# robotShield_USB.net
KiCad netlist of a schematic drawn in Altium Designer
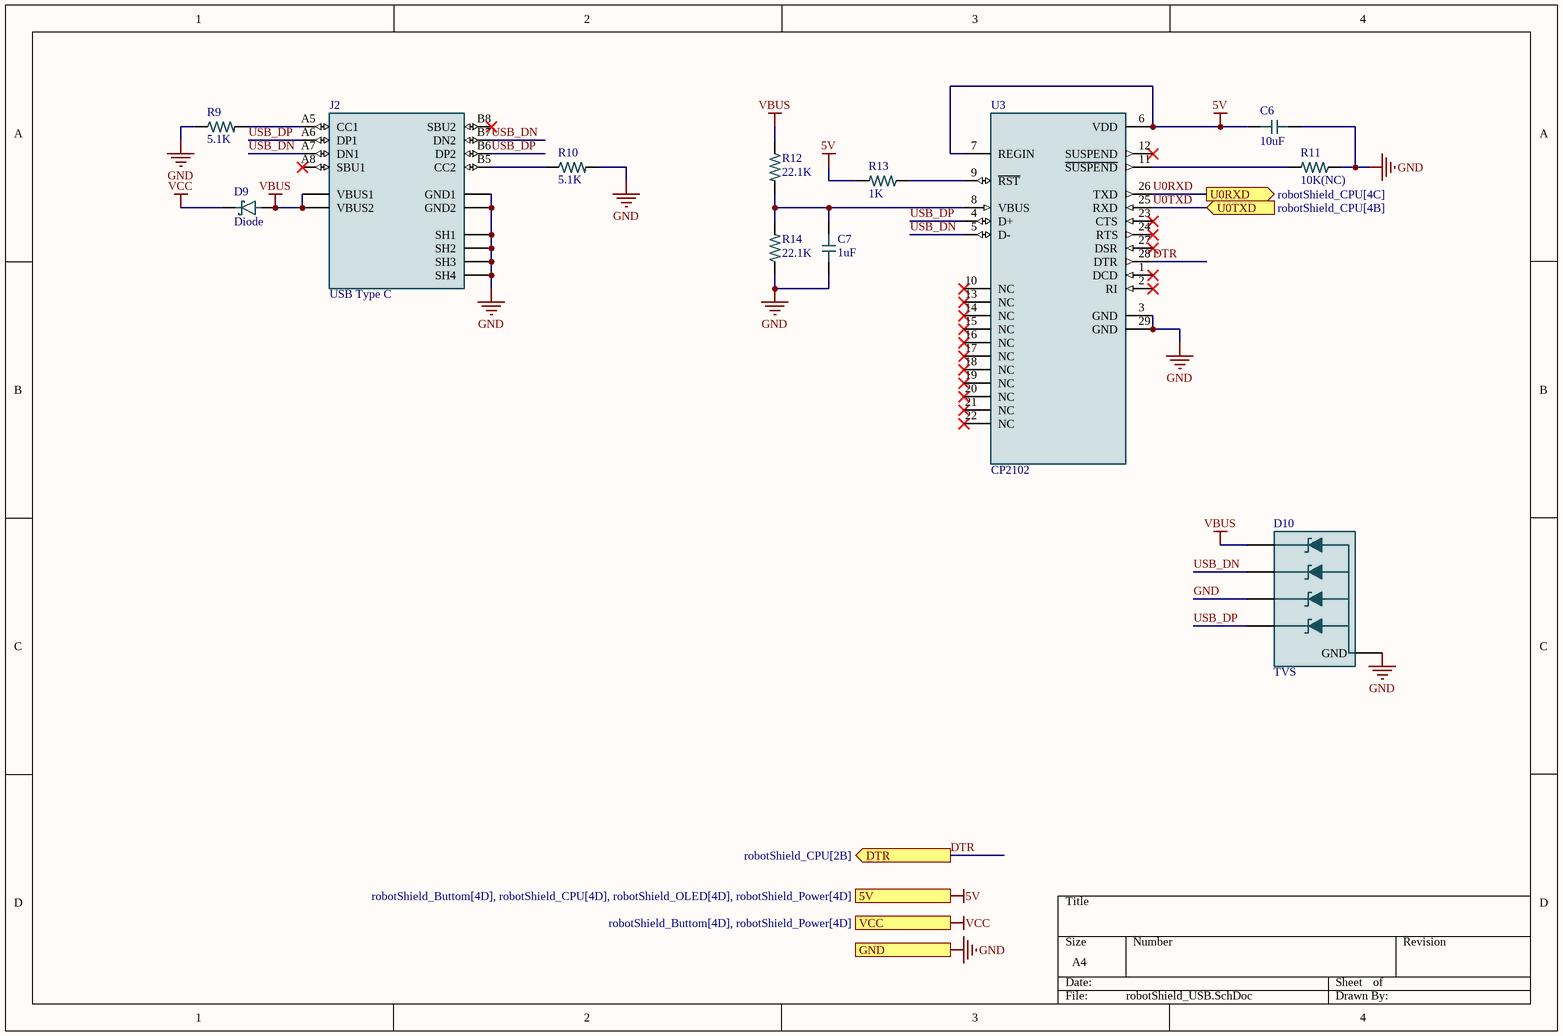
[diagram p0: robotShield_USB.SchDoc]

(export (version "E")
  (design (tool "Eeschema 10.0.6"))
  (components
    (comp (ref "C6")
      (value "10uF")
      (footprint "CAP0603")
      (description "CAP SMD")
      (fields (field (name "MF") "AVX") (field (name "MP") "LD031A101GAB2A"))
      (libsource (lib "Hossein72T") (part "Capacitor"))
    )
    (comp (ref "C7")
      (value "1uF")
      (footprint "CAP0603")
      (description "CAP SMD")
      (fields (field (name "MF") "AVX") (field (name "MP") "LD031A101GAB2A"))
      (libsource (lib "Hossein72T") (part "Capacitor"))
    )
    (comp (ref "D9")
      (value "Diode")
      (footprint "MBR0520LT3G")
      (description "Schottky Diode")
      (fields (field (name "MF") "Diotec Semiconductor") (field (name "MP") "S1M"))
      (libsource (lib "Hossein72T") (part "Schottky Diode"))
    )
    (comp (ref "D10")
      (value "TVS")
      (footprint "TVS-SE05T1D12GZ")
      (description "ESD8104MUTAG, Quad Uni-Directional ESD Protection Diode, 10-Pin UDFN")
      (fields (field (name "MP") "ESD8104MUTAG") (field (name "MF") "ON Semiconductor"))
      (libsource (lib "Hossein72T") (part "TVS_SE05NRC14GT"))
    )
    (comp (ref "J2")
      (value "USB Type C")
      (footprint "USB_Type_C_16pin")
      (description "USB Type C - Connector, Top-mount SMT, 16pos ¦ Molex Incorporated 217179-0001")
      (fields (field (name "MF") "Molex") (field (name "MP") "217179-0001"))
      (libsource (lib "Hossein72T") (part "USB_Type_C _16pin"))
    )
    (comp (ref "R9")
      (value "5.1K")
      (footprint "RES0603")
      (description "RES 0.27 OHM 1% 1/10W")
      (fields (field (name "MP") "3-1879460-5") (field (name "MF") "TE Connectivity"))
      (libsource (lib "Hossein72T") (part "Resistor"))
    )
    (comp (ref "R10")
      (value "5.1K")
      (footprint "RES0603")
      (description "RES 0.27 OHM 1% 1/10W")
      (fields (field (name "MP") "3-1879460-5") (field (name "MF") "TE Connectivity"))
      (libsource (lib "Hossein72T") (part "Resistor"))
    )
    (comp (ref "R11")
      (value "10K(NC)")
      (footprint "RES0603")
      (description "RES 0.27 OHM 1% 1/10W")
      (fields (field (name "MP") "3-1879460-5") (field (name "MF") "TE Connectivity"))
      (libsource (lib "Hossein72T") (part "Resistor"))
    )
    (comp (ref "R12")
      (value "22.1K")
      (footprint "RES0603")
      (description "RES 0.27 OHM 1% 1/10W")
      (fields (field (name "MP") "3-1879460-5") (field (name "MF") "TE Connectivity"))
      (libsource (lib "Hossein72T") (part "Resistor"))
    )
    (comp (ref "R13")
      (value "1K")
      (footprint "RES0603")
      (description "RES 0.27 OHM 1% 1/10W")
      (fields (field (name "MP") "3-1879460-5") (field (name "MF") "TE Connectivity"))
      (libsource (lib "Hossein72T") (part "Resistor"))
    )
    (comp (ref "R14")
      (value "22.1K")
      (footprint "RES0603")
      (description "RES 0.27 OHM 1% 1/10W")
      (fields (field (name "MP") "3-1879460-5") (field (name "MF") "TE Connectivity"))
      (libsource (lib "Hossein72T") (part "Resistor"))
    )
    (comp (ref "U3")
      (value "CP2102")
      (footprint "CP2102")
      (description "CP2102N USB 2.0 to UART (RS232) Bridge Interface Evaluation Board")
      (fields (field (name "MF") "Silicon Labs"))
      (libsource (lib "Hossein72T") (part "CP2102"))
    )
  )
  (nets
    (net (code "1") (name "/DTR") (class "Default")
      (node (ref "U3") (pin "28") (pinfunction "DTR_28") (pintype "output"))
    )
    (net (code "2") (name "/U0RXD") (class "Default")
      (node (ref "U3") (pin "26") (pinfunction "TXD_26") (pintype "output"))
    )
    (net (code "3") (name "/U0TXD") (class "Default")
      (node (ref "U3") (pin "25") (pinfunction "RXD_25") (pintype "input"))
    )
    (net (code "4") (name "/USB_DN") (class "Default")
      (node (ref "D10") (pin "2") (pinfunction "I/O_2_2") (pintype "passive"))
      (node (ref "J2") (pin "A7") (pinfunction "DN1_A7") (pintype "bidirectional"))
      (node (ref "J2") (pin "B7") (pinfunction "DN2_B7") (pintype "bidirectional"))
      (node (ref "U3") (pin "5") (pinfunction "D-_5") (pintype "bidirectional"))
    )
    (net (code "5") (name "/USB_DP") (class "Default")
      (node (ref "D10") (pin "5") (pinfunction "I/O_5_5") (pintype "passive"))
      (node (ref "J2") (pin "A6") (pinfunction "DP1_A6") (pintype "bidirectional"))
      (node (ref "J2") (pin "B6") (pinfunction "DP2_B6") (pintype "bidirectional"))
      (node (ref "U3") (pin "4") (pinfunction "D+_4") (pintype "bidirectional"))
    )
    (net (code "6") (name "5V") (class "Default")
      (node (ref "C6") (pin "1") (pinfunction "1_1") (pintype "passive"))
      (node (ref "R13") (pin "2") (pinfunction "2_2") (pintype "passive"))
      (node (ref "U3") (pin "6") (pinfunction "VDD_6") (pintype "power_in"))
      (node (ref "U3") (pin "7") (pinfunction "REGIN_7") (pintype "power_in"))
    )
    (net (code "7") (name "GND") (class "Default")
      (node (ref "C6") (pin "2") (pinfunction "2_2") (pintype "passive"))
      (node (ref "C7") (pin "2") (pinfunction "2_2") (pintype "passive"))
      (node (ref "D10") (pin "3") (pinfunction "GND_3") (pintype "power_in"))
      (node (ref "D10") (pin "4") (pinfunction "I/O_4_4") (pintype "passive"))
      (node (ref "J2") (pin "A1B12") (pinfunction "GND1_A1B12") (pintype "power_in"))
      (node (ref "J2") (pin "B1A12") (pinfunction "GND2_B1A12") (pintype "power_in"))
      (node (ref "J2") (pin "SH1") (pinfunction "SH1_SH1") (pintype "passive"))
      (node (ref "J2") (pin "SH2") (pinfunction "SH2_SH2") (pintype "passive"))
      (node (ref "J2") (pin "SH3") (pinfunction "SH3_SH3") (pintype "passive"))
      (node (ref "J2") (pin "SH4") (pinfunction "SH4_SH4") (pintype "passive"))
      (node (ref "R10") (pin "2") (pinfunction "2_2") (pintype "passive"))
      (node (ref "R11") (pin "1") (pinfunction "1_1") (pintype "passive"))
      (node (ref "R14") (pin "1") (pinfunction "1_1") (pintype "passive"))
      (node (ref "R9") (pin "1") (pinfunction "1_1") (pintype "passive"))
      (node (ref "U3") (pin "29") (pinfunction "GND_29") (pintype "power_in"))
      (node (ref "U3") (pin "3") (pinfunction "GND_3") (pintype "power_in"))
    )
    (net (code "8") (name "Net-(J2-CC1)") (class "Default")
      (node (ref "J2") (pin "A5") (pinfunction "CC1_A5") (pintype "bidirectional"))
      (node (ref "R9") (pin "2") (pinfunction "2_2") (pintype "passive"))
    )
    (net (code "9") (name "Net-(J2-CC2)") (class "Default")
      (node (ref "J2") (pin "B5") (pinfunction "CC2_B5") (pintype "bidirectional"))
      (node (ref "R10") (pin "1") (pinfunction "1_1") (pintype "passive"))
    )
    (net (code "10") (name "Net-(U3-VBUS)") (class "Default")
      (node (ref "C7") (pin "1") (pinfunction "1_1") (pintype "passive"))
      (node (ref "R12") (pin "2") (pinfunction "2_2") (pintype "passive"))
      (node (ref "R14") (pin "2") (pinfunction "2_2") (pintype "passive"))
      (node (ref "U3") (pin "8") (pinfunction "VBUS_8") (pintype "input"))
    )
    (net (code "11") (name "Net-(U3-~{RST})") (class "Default")
      (node (ref "R13") (pin "1") (pinfunction "1_1") (pintype "passive"))
      (node (ref "U3") (pin "9") (pinfunction "~{RST}_9") (pintype "bidirectional"))
    )
    (net (code "12") (name "Net-(U3-~{SUSPEND})") (class "Default")
      (node (ref "R11") (pin "2") (pinfunction "2_2") (pintype "passive"))
      (node (ref "U3") (pin "11") (pinfunction "~{SUSPEND}_11") (pintype "output"))
    )
    (net (code "13") (name "VBUS") (class "Default")
      (node (ref "D10") (pin "1") (pinfunction "I/O_1_1") (pintype "passive"))
      (node (ref "D9") (pin "A") (pinfunction "A_A") (pintype "passive"))
      (node (ref "J2") (pin "A4B9") (pinfunction "VBUS1_A4B9") (pintype "power_in"))
      (node (ref "J2") (pin "B4A9") (pinfunction "VBUS2_B4A9") (pintype "power_in"))
      (node (ref "R12") (pin "1") (pinfunction "1_1") (pintype "passive"))
    )
    (net (code "14") (name "VCC") (class "Default")
      (node (ref "D9") (pin "C") (pinfunction "K_C") (pintype "passive"))
    )
    (net (code "15") (name "unconnected-(J2-SBU1-PadA8)") (class "Default")
      (node (ref "J2") (pin "A8") (pinfunction "SBU1_A8") (pintype "bidirectional+no_connect"))
    )
    (net (code "16") (name "unconnected-(J2-SBU2-PadB8)") (class "Default")
      (node (ref "J2") (pin "B8") (pinfunction "SBU2_B8") (pintype "bidirectional+no_connect"))
    )
    (net (code "17") (name "unconnected-(U3-CTS-Pad23)") (class "Default")
      (node (ref "U3") (pin "23") (pinfunction "CTS_23") (pintype "input+no_connect"))
    )
    (net (code "18") (name "unconnected-(U3-DCD-Pad1)") (class "Default")
      (node (ref "U3") (pin "1") (pinfunction "DCD_1") (pintype "input+no_connect"))
    )
    (net (code "19") (name "unconnected-(U3-DSR-Pad27)") (class "Default")
      (node (ref "U3") (pin "27") (pinfunction "DSR_27") (pintype "input+no_connect"))
    )
    (net (code "20") (name "unconnected-(U3-NC-Pad10)") (class "Default")
      (node (ref "U3") (pin "10") (pinfunction "NC_10") (pintype "passive+no_connect"))
    )
    (net (code "21") (name "unconnected-(U3-NC-Pad13)") (class "Default")
      (node (ref "U3") (pin "13") (pinfunction "NC_13") (pintype "passive+no_connect"))
    )
    (net (code "22") (name "unconnected-(U3-NC-Pad14)") (class "Default")
      (node (ref "U3") (pin "14") (pinfunction "NC_14") (pintype "passive+no_connect"))
    )
    (net (code "23") (name "unconnected-(U3-NC-Pad15)") (class "Default")
      (node (ref "U3") (pin "15") (pinfunction "NC_15") (pintype "passive+no_connect"))
    )
    (net (code "24") (name "unconnected-(U3-NC-Pad16)") (class "Default")
      (node (ref "U3") (pin "16") (pinfunction "NC_16") (pintype "passive+no_connect"))
    )
    (net (code "25") (name "unconnected-(U3-NC-Pad17)") (class "Default")
      (node (ref "U3") (pin "17") (pinfunction "NC_17") (pintype "passive+no_connect"))
    )
    (net (code "26") (name "unconnected-(U3-NC-Pad18)") (class "Default")
      (node (ref "U3") (pin "18") (pinfunction "NC_18") (pintype "passive+no_connect"))
    )
    (net (code "27") (name "unconnected-(U3-NC-Pad19)") (class "Default")
      (node (ref "U3") (pin "19") (pinfunction "NC_19") (pintype "passive+no_connect"))
    )
    (net (code "28") (name "unconnected-(U3-NC-Pad20)") (class "Default")
      (node (ref "U3") (pin "20") (pinfunction "NC_20") (pintype "passive+no_connect"))
    )
    (net (code "29") (name "unconnected-(U3-NC-Pad21)") (class "Default")
      (node (ref "U3") (pin "21") (pinfunction "NC_21") (pintype "passive+no_connect"))
    )
    (net (code "30") (name "unconnected-(U3-NC-Pad22)") (class "Default")
      (node (ref "U3") (pin "22") (pinfunction "NC_22") (pintype "passive+no_connect"))
    )
    (net (code "31") (name "unconnected-(U3-RI-Pad2)") (class "Default")
      (node (ref "U3") (pin "2") (pinfunction "RI_2") (pintype "input+no_connect"))
    )
    (net (code "32") (name "unconnected-(U3-RTS-Pad24)") (class "Default")
      (node (ref "U3") (pin "24") (pinfunction "RTS_24") (pintype "output+no_connect"))
    )
    (net (code "33") (name "unconnected-(U3-SUSPEND-Pad12)") (class "Default")
      (node (ref "U3") (pin "12") (pinfunction "SUSPEND_12") (pintype "output+no_connect"))
    )
  )
)
